# SCH_Led-Chaser_2025-11-02.net
KiCad netlist of a schematic drawn in EasyEDA
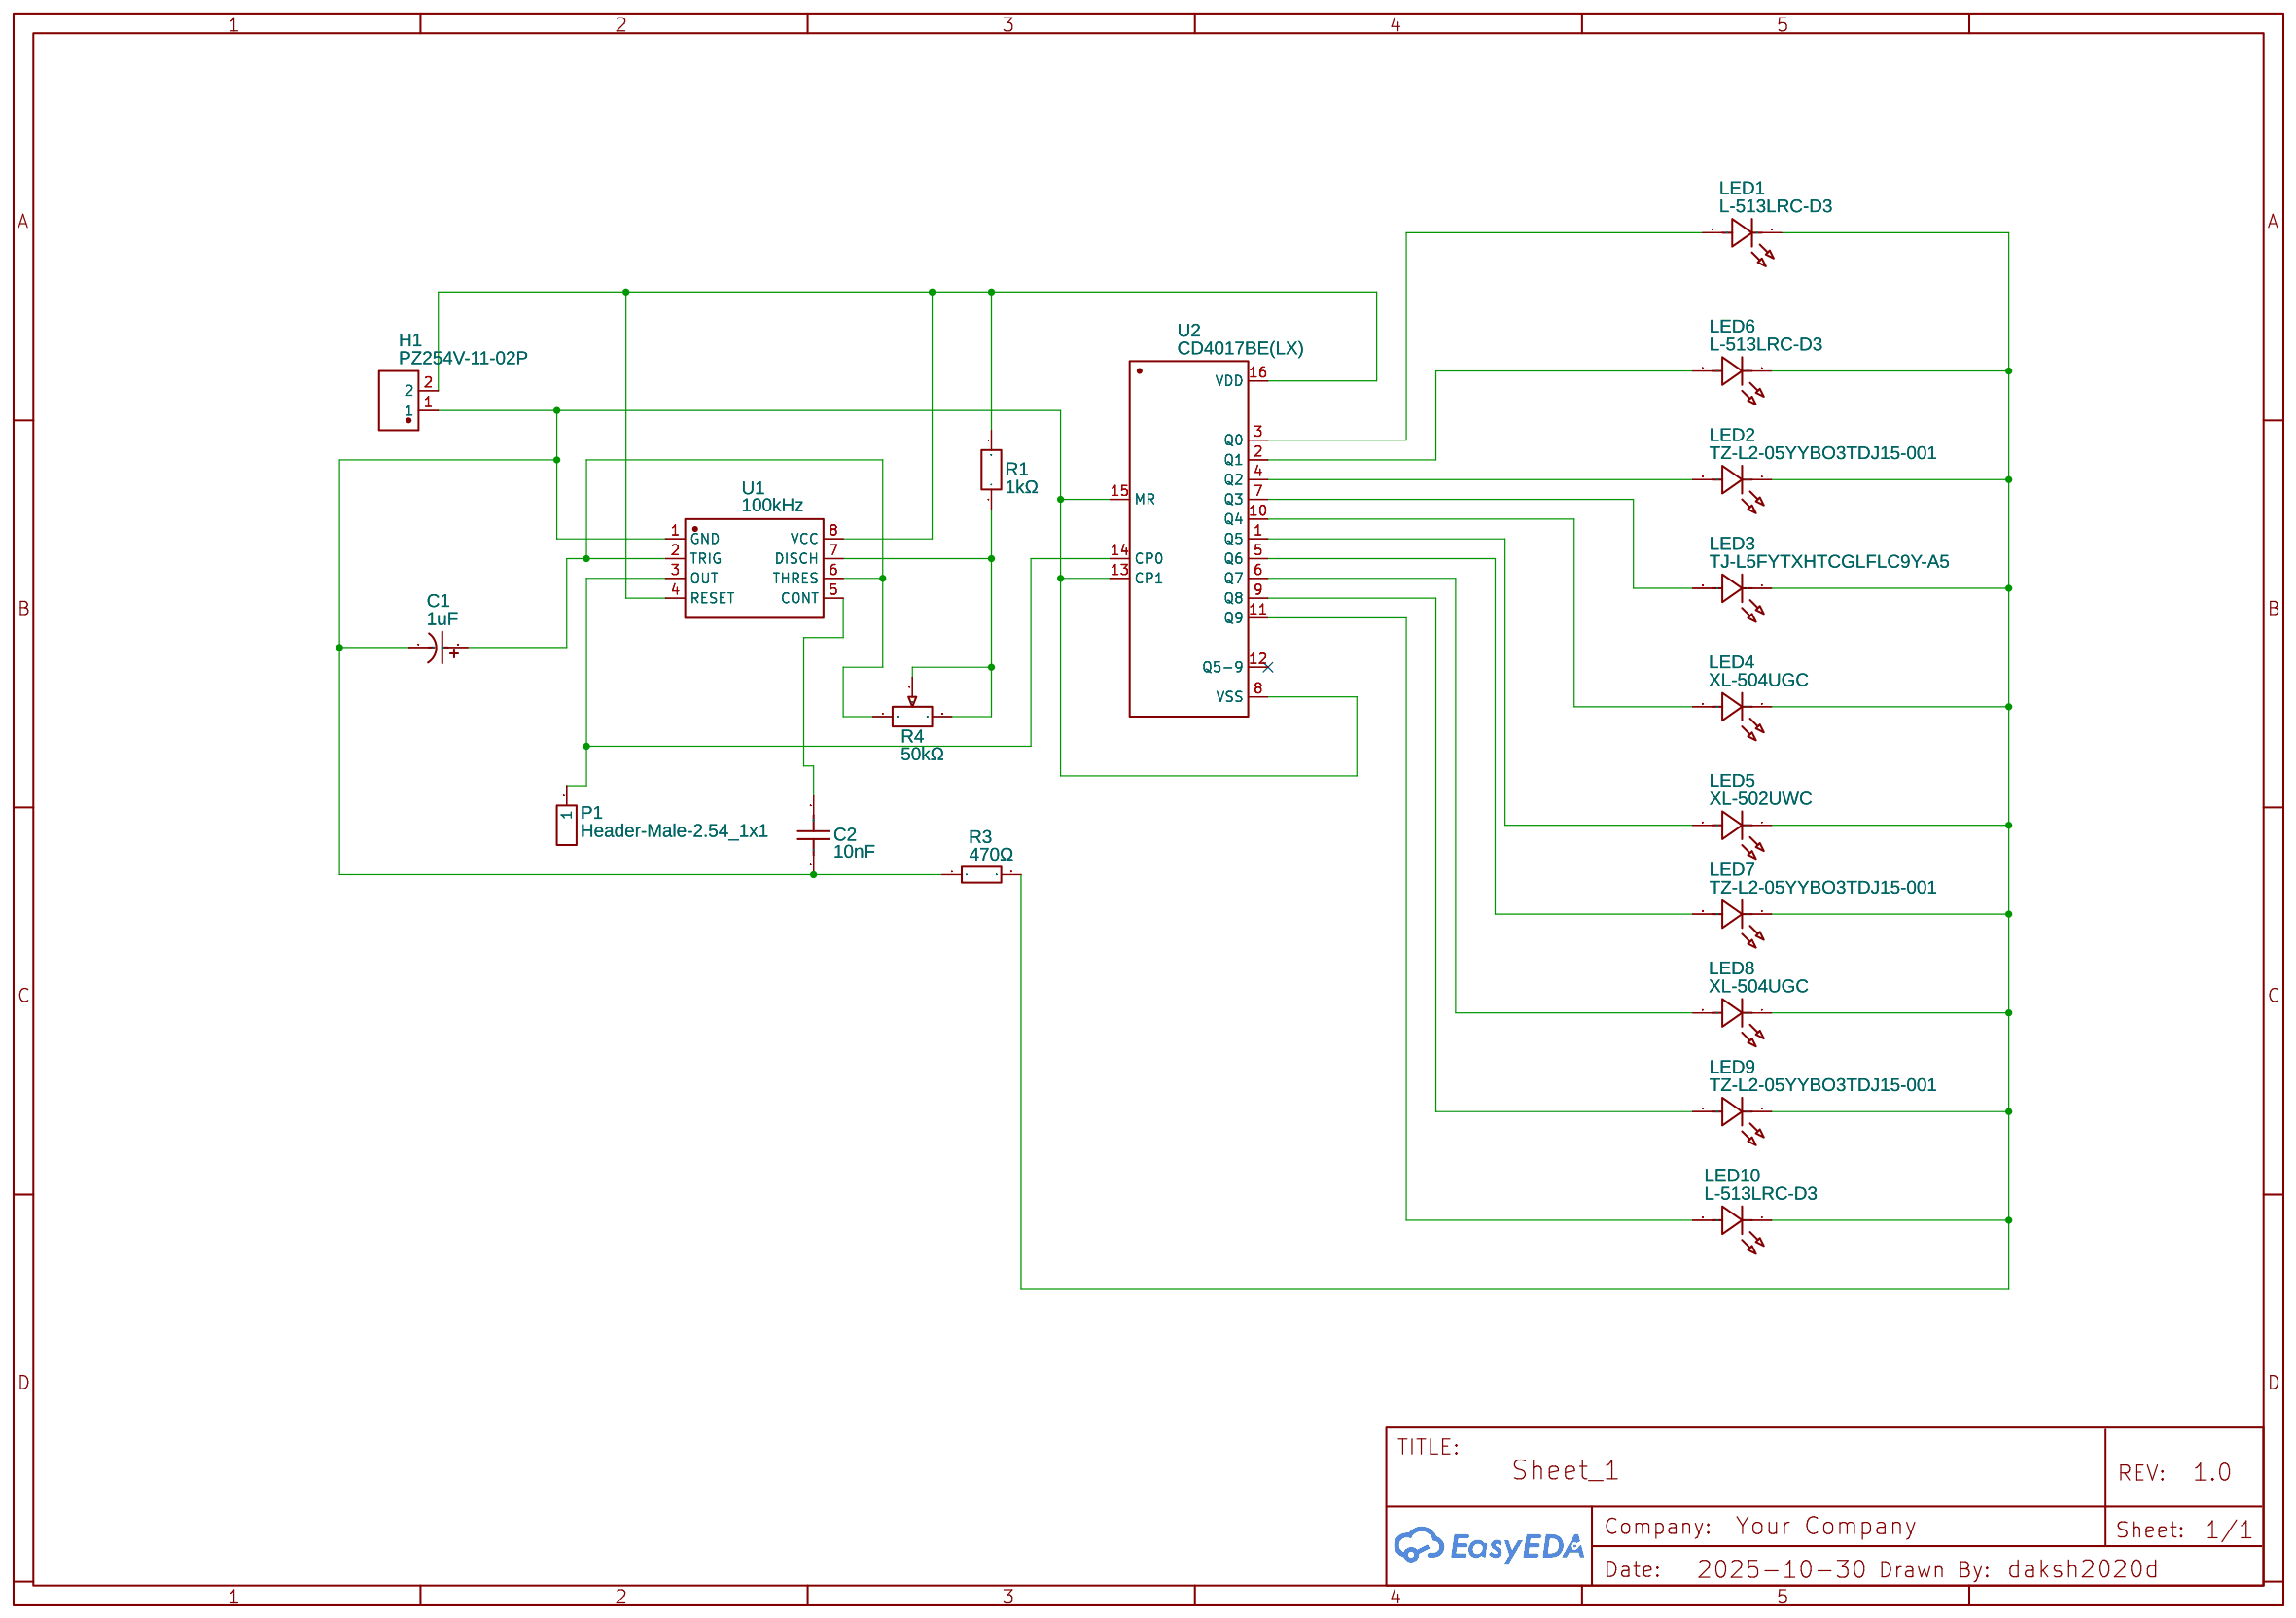
[diagram p0: schematic sheet]

(export (version "E")
  (design (tool "Eeschema 10.0.6"))
  (components
    (comp (ref "C1")
      (value "1uF")
      (fields (field (name "Manufacturer Part") "KF010M050C110A") (field (name "Manufacturer") "CapXon(丰宾)"))
      (libsource (lib "") (part "KF010M050C110A"))
    )
    (comp (ref "C2")
      (value "10nF")
      (fields (field (name "Manufacturer Part") "N09F1B103MN0B0S0N0") (field (name "Manufacturer") "STE(松田)"))
      (libsource (lib "") (part "N09F1B103MN0B0S0N0"))
    )
    (comp (ref "H1")
      (value "PZ254V-11-02P")
      (fields (field (name "Manufacturer") "XFCN(兴飞)"))
      (libsource (lib "") (part "PZ254V-11-02P"))
    )
    (comp (ref "LED1")
      (value "L-513LRC-D3")
      (fields (field (name "Manufacturer") "PARALIGHT(光鼎)"))
      (libsource (lib "") (part "L-513LRC-D3"))
    )
    (comp (ref "LED2")
      (value "TZ-L2-05YYBO3TDJ15-001")
      (fields (field (name "Manufacturer") "TUOZHAN(拓展光电)"))
      (libsource (lib "") (part "TZ-L2-05YYBO3TDJ15-001"))
    )
    (comp (ref "LED3")
      (value "TJ-L5FYTXHTCGLFLC9Y-A5")
      (fields (field (name "Manufacturer") "TOGIALED(统佳)"))
      (libsource (lib "") (part "TJ-L5FYTXHTCGLFLC9Y-A5"))
    )
    (comp (ref "LED4")
      (value "XL-504UGC")
      (fields (field (name "Manufacturer") "XINGLIGHT(成兴光)"))
      (libsource (lib "") (part "XL-504UGC"))
    )
    (comp (ref "LED5")
      (value "XL-502UWC")
      (fields (field (name "Manufacturer") "XINGLIGHT(成兴光)"))
      (libsource (lib "") (part "XL-502UWC"))
    )
    (comp (ref "LED6")
      (value "L-513LRC-D3")
      (fields (field (name "Manufacturer") "PARALIGHT(光鼎)"))
      (libsource (lib "") (part "L-513LRC-D3"))
    )
    (comp (ref "LED7")
      (value "TZ-L2-05YYBO3TDJ15-001")
      (fields (field (name "Manufacturer") "TUOZHAN(拓展光电)"))
      (libsource (lib "") (part "TZ-L2-05YYBO3TDJ15-001"))
    )
    (comp (ref "LED8")
      (value "XL-504UGC")
      (fields (field (name "Manufacturer") "XINGLIGHT(成兴光)"))
      (libsource (lib "") (part "XL-504UGC"))
    )
    (comp (ref "LED9")
      (value "TZ-L2-05YYBO3TDJ15-001")
      (fields (field (name "Manufacturer") "TUOZHAN(拓展光电)"))
      (libsource (lib "") (part "TZ-L2-05YYBO3TDJ15-001"))
    )
    (comp (ref "LED10")
      (value "L-513LRC-D3")
      (fields (field (name "Manufacturer") "PARALIGHT(光鼎)"))
      (libsource (lib "") (part "L-513LRC-D3"))
    )
    (comp (ref "P1")
      (value "Header-Male-2.54_1x1")
      (fields (field (name "Manufacturer Part") "2.54-1*1P针") (field (name "Manufacturer") "BOOMELE(博穆精密)"))
      (libsource (lib "") (part "Header-Male-2.54_1x1"))
    )
    (comp (ref "R1")
      (value "1kΩ")
      (fields (field (name "Manufacturer Part") "MF1/4W-1KΩ±1%T52") (field (name "Manufacturer") "华星机电"))
      (libsource (lib "") (part "MF1/4W-1KΩ±1%T52"))
    )
    (comp (ref "R3")
      (value "470Ω")
      (fields
        (field (name "Manufacturer Part") "MFR0W4F4700A50")
        (field (name "Manufacturer") "UNI-ROYAL(厚声)")
      )
      (libsource (lib "") (part "MFR0W4F4700A50"))
    )
    (comp (ref "R4")
      (value "50kΩ")
      (fields (field (name "Manufacturer Part") "3296X-1-503") (field (name "Manufacturer") "BOCHEN(博晨)"))
      (libsource (lib "") (part "3296X-1-503_C118912"))
    )
    (comp (ref "U1")
      (value "100kHz")
      (fields (field (name "Manufacturer Part") "NE555P") (field (name "Manufacturer") "TI(德州仪器)"))
      (libsource (lib "") (part "NE555P"))
    )
    (comp (ref "U2")
      (value "CD4017BE(LX)")
      (fields (field (name "Manufacturer") "LX(灵星芯微)"))
      (libsource (lib "") (part "CD4017BE(LX)"))
    )
  )
  (nets
    (net (code "1") (name "Net-(LED1-A)") (class "Default")
      (node (ref "LED1") (pin "2") (pinfunction "A_2") (pintype "unspecified"))
      (node (ref "U2") (pin "3") (pinfunction "Q0_3") (pintype "unspecified"))
    )
    (net (code "2") (name "Net-(LED1-K)") (class "Default")
      (node (ref "LED1") (pin "1") (pinfunction "K_1") (pintype "unspecified"))
      (node (ref "LED10") (pin "1") (pinfunction "K_1") (pintype "unspecified"))
      (node (ref "LED2") (pin "1") (pinfunction "-_1") (pintype "unspecified"))
      (node (ref "LED3") (pin "1") (pinfunction "-_1") (pintype "unspecified"))
      (node (ref "LED4") (pin "1") (pinfunction "K_1") (pintype "unspecified"))
      (node (ref "LED5") (pin "1") (pinfunction "K_1") (pintype "unspecified"))
      (node (ref "LED6") (pin "1") (pinfunction "K_1") (pintype "unspecified"))
      (node (ref "LED7") (pin "1") (pinfunction "-_1") (pintype "unspecified"))
      (node (ref "LED8") (pin "1") (pinfunction "K_1") (pintype "unspecified"))
      (node (ref "LED9") (pin "1") (pinfunction "-_1") (pintype "unspecified"))
      (node (ref "R3") (pin "2") (pinfunction "2_2") (pintype "input"))
    )
    (net (code "3") (name "Net-(LED2-+)") (class "Default")
      (node (ref "LED2") (pin "2") (pinfunction "+_2") (pintype "unspecified"))
      (node (ref "U2") (pin "4") (pinfunction "Q2_4") (pintype "unspecified"))
    )
    (net (code "4") (name "Net-(LED3-+)") (class "Default")
      (node (ref "LED3") (pin "2") (pinfunction "+_2") (pintype "unspecified"))
      (node (ref "U2") (pin "7") (pinfunction "Q3_7") (pintype "unspecified"))
    )
    (net (code "5") (name "Net-(LED4-A)") (class "Default")
      (node (ref "LED4") (pin "2") (pinfunction "A_2") (pintype "unspecified"))
      (node (ref "U2") (pin "10") (pinfunction "Q4_10") (pintype "unspecified"))
    )
    (net (code "6") (name "Net-(LED5-A)") (class "Default")
      (node (ref "LED5") (pin "2") (pinfunction "A_2") (pintype "unspecified"))
      (node (ref "U2") (pin "1") (pinfunction "Q5_1") (pintype "unspecified"))
    )
    (net (code "7") (name "Net-(LED6-A)") (class "Default")
      (node (ref "LED6") (pin "2") (pinfunction "A_2") (pintype "unspecified"))
      (node (ref "U2") (pin "2") (pinfunction "Q1_2") (pintype "unspecified"))
    )
    (net (code "8") (name "Net-(LED7-+)") (class "Default")
      (node (ref "LED7") (pin "2") (pinfunction "+_2") (pintype "unspecified"))
      (node (ref "U2") (pin "5") (pinfunction "Q6_5") (pintype "unspecified"))
    )
    (net (code "9") (name "Net-(LED8-A)") (class "Default")
      (node (ref "LED8") (pin "2") (pinfunction "A_2") (pintype "unspecified"))
      (node (ref "U2") (pin "6") (pinfunction "Q7_6") (pintype "unspecified"))
    )
    (net (code "10") (name "Net-(LED9-+)") (class "Default")
      (node (ref "LED9") (pin "2") (pinfunction "+_2") (pintype "unspecified"))
      (node (ref "U2") (pin "9") (pinfunction "Q8_9") (pintype "unspecified"))
    )
    (net (code "11") (name "Net-(LED10-A)") (class "Default")
      (node (ref "LED10") (pin "2") (pinfunction "A_2") (pintype "unspecified"))
      (node (ref "U2") (pin "11") (pinfunction "Q9_11") (pintype "unspecified"))
    )
    (net (code "12") (name "Net-(U1-CONT)") (class "Default")
      (node (ref "C2") (pin "2") (pinfunction "2_2") (pintype "unspecified"))
      (node (ref "U1") (pin "5") (pinfunction "CONT_5") (pintype "unspecified"))
    )
    (net (code "13") (name "Net-(U1-DISCH)") (class "Default")
      (node (ref "R1") (pin "1") (pinfunction "1_1") (pintype "unspecified"))
      (node (ref "R4") (pin "2") (pinfunction "2_2") (pintype "input"))
      (node (ref "R4") (pin "3") (pinfunction "3_3") (pintype "input"))
      (node (ref "U1") (pin "7") (pinfunction "DISCH_7") (pintype "unspecified"))
    )
    (net (code "14") (name "Net-(U1-GND)") (class "Default")
      (node (ref "C1") (pin "2") (pinfunction "2_2") (pintype "input"))
      (node (ref "C2") (pin "1") (pinfunction "1_1") (pintype "unspecified"))
      (node (ref "H1") (pin "1") (pinfunction "1_1") (pintype "unspecified"))
      (node (ref "R3") (pin "1") (pinfunction "1_1") (pintype "input"))
      (node (ref "U1") (pin "1") (pinfunction "GND_1") (pintype "unspecified"))
      (node (ref "U2") (pin "13") (pinfunction "CP1_13") (pintype "unspecified"))
      (node (ref "U2") (pin "15") (pinfunction "MR_15") (pintype "unspecified"))
      (node (ref "U2") (pin "8") (pinfunction "VSS_8") (pintype "unspecified"))
    )
    (net (code "15") (name "Net-(U1-OUT)") (class "Default")
      (node (ref "P1") (pin "1") (pinfunction "1_1") (pintype "input"))
      (node (ref "U1") (pin "3") (pinfunction "OUT_3") (pintype "unspecified"))
      (node (ref "U2") (pin "14") (pinfunction "CP0_14") (pintype "unspecified"))
    )
    (net (code "16") (name "Net-(U1-RESET)") (class "Default")
      (node (ref "H1") (pin "2") (pinfunction "2_2") (pintype "unspecified"))
      (node (ref "R1") (pin "2") (pinfunction "2_2") (pintype "unspecified"))
      (node (ref "U1") (pin "4") (pinfunction "RESET_4") (pintype "unspecified"))
      (node (ref "U1") (pin "8") (pinfunction "VCC_8") (pintype "unspecified"))
      (node (ref "U2") (pin "16") (pinfunction "VDD_16") (pintype "unspecified"))
    )
    (net (code "17") (name "Net-(U1-THRES)") (class "Default")
      (node (ref "C1") (pin "1") (pinfunction "1_1") (pintype "input"))
      (node (ref "R4") (pin "1") (pinfunction "1_1") (pintype "input"))
      (node (ref "U1") (pin "2") (pinfunction "TRIG_2") (pintype "unspecified"))
      (node (ref "U1") (pin "6") (pinfunction "THRES_6") (pintype "unspecified"))
    )
    (net (code "18") (name "unconnected-(U2-Q5-9-Pad12)") (class "Default")
      (node (ref "U2") (pin "12") (pinfunction "Q5-9_12") (pintype "unspecified+no_connect"))
    )
  )
)
